# 2_rain_oca_2020.net
KiCad netlist of a schematic drawn in EAGLE
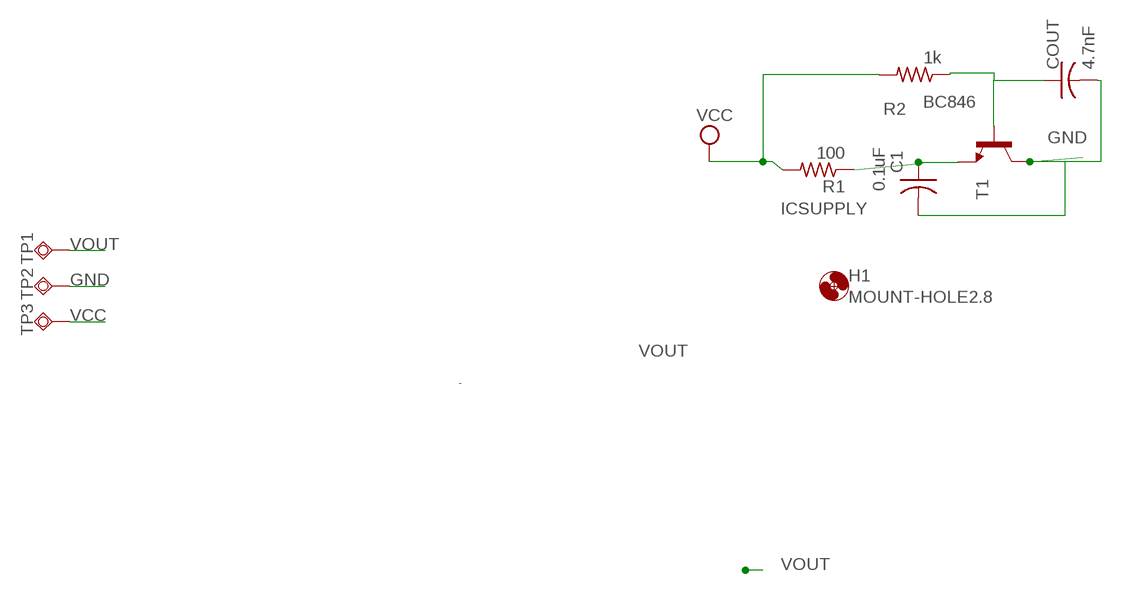
[diagram p0: schematic, sheet 1]

(export (version "E")
  (design (tool "Eeschema 10.0.6"))
  (components
    (comp (ref "C1")
      (value "0.1uF")
      (footprint "eagle-import:C0402")
      (libsource (lib "eagle-import") (part "C-USC0402"))
    )
    (comp (ref "COUT")
      (value "4.7nF")
      (footprint "eagle-import:C0402")
      (libsource (lib "eagle-import") (part "C-USC0402"))
    )
    (comp (ref "H1")
      (value "MOUNT-HOLE2.8")
      (footprint "eagle-import:2,8")
      (libsource (lib "eagle-import") (part "MOUNT-HOLE2.8"))
    )
    (comp (ref "R1")
      (value "100")
      (footprint "eagle-import:R0603")
      (libsource (lib "eagle-import") (part "R-US_R0603"))
    )
    (comp (ref "R2")
      (value "1k")
      (footprint "eagle-import:R0603")
      (libsource (lib "eagle-import") (part "R-US_R0603"))
    )
    (comp (ref "T1")
      (value "BC846")
      (footprint "eagle-import:SOT23")
      (libsource (lib "eagle-import") (part "BC846"))
    )
    (comp (ref "TP1")
      (value "TPSQTP20SQ")
      (footprint "eagle-import:TP20SQ")
      (libsource (lib "eagle-import") (part "TPSQTP20SQ"))
    )
    (comp (ref "TP2")
      (value "TPSQTP20SQ")
      (footprint "eagle-import:TP20SQ")
      (libsource (lib "eagle-import") (part "TPSQTP20SQ"))
    )
    (comp (ref "TP3")
      (value "TPSQTP20SQ")
      (footprint "eagle-import:TP20SQ")
      (libsource (lib "eagle-import") (part "TPSQTP20SQ"))
    )
  )
  (nets
    (net (code "1") (name "/GND") (class "Default")
      (node (ref "C1") (pin "2") (pinfunction "2_2") (pintype "passive"))
      (node (ref "COUT") (pin "2") (pinfunction "2_2") (pintype "passive"))
      (node (ref "T1") (pin "3") (pinfunction "C_3") (pintype "passive"))
      (node (ref "TP2") (pin "TP") (pinfunction "TP_TP") (pintype "input"))
    )
    (net (code "2") (name "/ICSUPPLY") (class "Default")
      (node (ref "C1") (pin "1") (pinfunction "1_1") (pintype "passive"))
      (node (ref "R1") (pin "1") (pinfunction "1_1") (pintype "passive"))
      (node (ref "T1") (pin "2") (pinfunction "E_2") (pintype "passive"))
    )
    (net (code "3") (name "/VOUT") (class "Default")
      (node (ref "COUT") (pin "1") (pinfunction "1_1") (pintype "passive"))
      (node (ref "R2") (pin "1") (pinfunction "1_1") (pintype "passive"))
      (node (ref "T1") (pin "1") (pinfunction "B_1") (pintype "passive"))
      (node (ref "TP1") (pin "TP") (pinfunction "TP_TP") (pintype "input"))
    )
    (net (code "4") (name "VCC") (class "Default")
      (node (ref "R1") (pin "2") (pinfunction "2_2") (pintype "passive"))
      (node (ref "R2") (pin "2") (pinfunction "2_2") (pintype "passive"))
      (node (ref "TP3") (pin "TP") (pinfunction "TP_TP") (pintype "input"))
    )
  )
)
